# MAGI_sBuckPower-TEST_-.net
KiCad netlist of a schematic drawn in Altium Designer
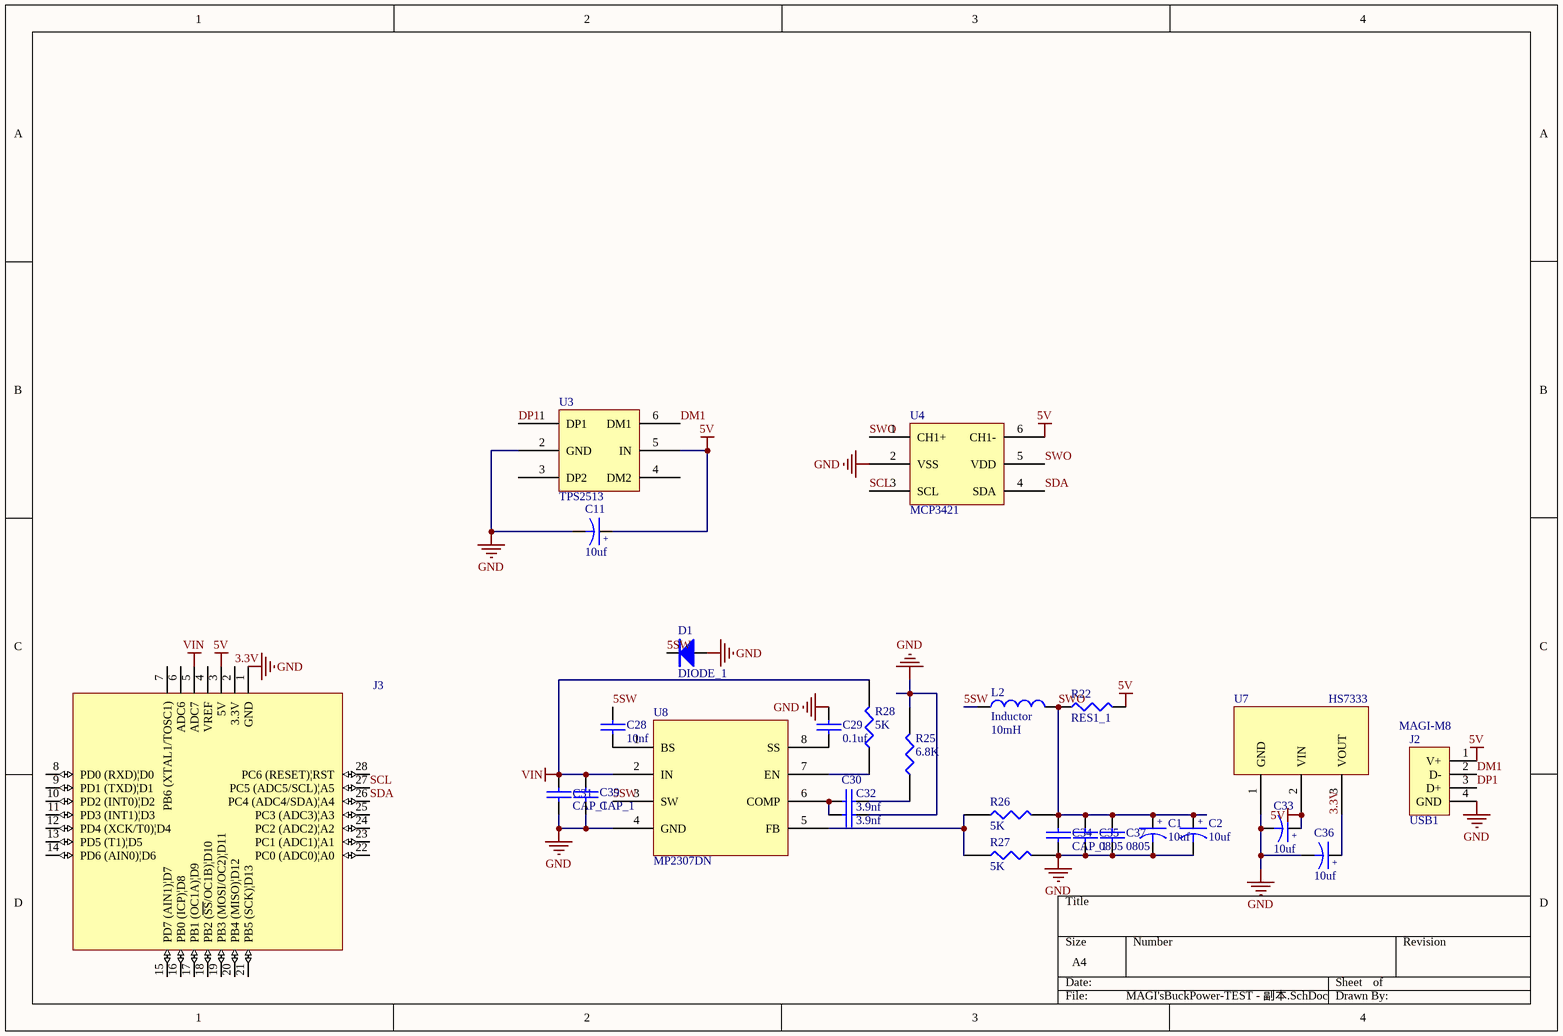
[diagram p0: MAGI'sBuckPower-TEST - 副本.SchDoc]

(export (version "E")
  (design (tool "Eeschema 10.0.6"))
  (components
    (comp (ref "C1")
      (value "10uf")
      (footprint "C1210_N")
      (description "Capacitor")
      (libsource (lib "电容器") (part "CAPACITOR POL"))
    )
    (comp (ref "C2")
      (value "10uf")
      (footprint "C1210_N")
      (description "Capacitor")
      (libsource (lib "电容器") (part "CAPACITOR POL"))
    )
    (comp (ref "C11")
      (value "10uf")
      (footprint "6-0805_N")
      (description "Capacitor")
      (libsource (lib "电容器") (part "CAPACITOR POL"))
    )
    (comp (ref "C28")
      (value "10nf")
      (footprint "6-0805_N")
      (description "Capacitor")
      (libsource (lib "电容器") (part "CAP_1"))
    )
    (comp (ref "C29")
      (value "0.1uf")
      (footprint "6-0805_N")
      (description "Capacitor")
      (libsource (lib "电容器") (part "CAP_1"))
    )
    (comp (ref "C30")
      (value "3.9nf")
      (footprint "6-0805_N")
      (description "Capacitor")
      (libsource (lib "电容器") (part "CAP_1"))
    )
    (comp (ref "C31")
      (value "CAP_1")
      (footprint "C1206")
      (description "Capacitor")
      (libsource (lib "电容器") (part "CAP_1"))
    )
    (comp (ref "C32")
      (value "3.9nf")
      (footprint "6-0805_N")
      (description "Capacitor")
      (libsource (lib "电容器") (part "CAP_1"))
    )
    (comp (ref "C33")
      (value "10uf")
      (footprint "6-0805_N")
      (description "Capacitor")
      (libsource (lib "电容器") (part "CAPACITOR POL"))
    )
    (comp (ref "C34")
      (value "CAP_1")
      (footprint "6TPE330M")
      (description "Capacitor")
      (libsource (lib "电容器") (part "CAP_1"))
    )
    (comp (ref "C35")
      (value "0805")
      (footprint "6-0805_N")
      (description "Capacitor")
      (libsource (lib "电容器") (part "CAP_1"))
    )
    (comp (ref "C36")
      (value "10uf")
      (footprint "6-0805_N")
      (description "Capacitor")
      (libsource (lib "电容器") (part "CAPACITOR POL"))
    )
    (comp (ref "C37")
      (value "0805")
      (footprint "6-0805_N")
      (description "Capacitor")
      (libsource (lib "电容器") (part "CAP_1"))
    )
    (comp (ref "C39")
      (value "CAP_1")
      (footprint "C1206")
      (description "Capacitor")
      (libsource (lib "电容器") (part "CAP_1"))
    )
    (comp (ref "D1")
      (value "DIODE_1")
      (footprint "SMA")
      (description "Diode")
      (libsource (lib "二极管") (part "DIODE_1"))
    )
    (comp (ref "J2") (value "USB1") (footprint "USB-04A") (libsource (lib "USB接口") (part "USB1")))
    (comp (ref "J3") (value "MAGI-M8") (footprint "MAGIsBoard") (libsource (lib "MAGI-M8") (part "MAGI-M8")))
    (comp (ref "L2")
      (value "Inductor")
      (footprint "7*7")
      (fields (field (name "ALTIUM_VALUE") "10mH") (field (name "PUBLISHER") "Altium Limited"))
      (libsource (lib "Miscellaneous Devices") (part "Inductor"))
    )
    (comp (ref "R22") (value "RES1_1") (footprint "2512") (libsource (lib "电阻器") (part "RES1_1")))
    (comp (ref "R25") (value "6.8K") (footprint "6-0805_N") (libsource (lib "电阻器") (part "RES1")))
    (comp (ref "R26") (value "5K") (footprint "6-0805_N") (libsource (lib "电阻器") (part "RES1")))
    (comp (ref "R27") (value "5K") (footprint "6-0805_N") (libsource (lib "电阻器") (part "RES1")))
    (comp (ref "R28") (value "5K") (footprint "6-0805_N") (libsource (lib "电阻器") (part "RES1")))
    (comp (ref "U3") (value "TPS2513") (footprint "TPS2513") (libsource (lib "PMIC") (part "TPS2513")))
    (comp (ref "U4") (value "MCP3421") (footprint "tps2513") (libsource (lib "ADC") (part "MCP3421")))
    (comp (ref "U7") (value "HS7333") (footprint "HS7333") (libsource (lib "PMIC") (part "HS7333")))
    (comp (ref "U8")
      (value "MP2307DN")
      (footprint "MP2307DN")
      (libsource (lib "MP2307Test") (part "MP2307DN"))
    )
  )
  (nets
    (net (code "1") (name "/3.3V") (class "Default")
      (node (ref "C36") (pin "1") (pinfunction "1_1") (pintype "passive"))
      (node (ref "J3") (pin "2") (pinfunction "3.3V_2") (pintype "power_in"))
      (node (ref "U7") (pin "3") (pinfunction "VOUT_3") (pintype "passive"))
    )
    (net (code "2") (name "/5SW") (class "Default")
      (node (ref "C28") (pin "1") (pinfunction "1_1") (pintype "passive"))
      (node (ref "D1") (pin "1") (pinfunction "K_1") (pintype "passive"))
      (node (ref "L2") (pin "1") (pinfunction "1_1") (pintype "passive"))
      (node (ref "U8") (pin "3") (pinfunction "SW_3") (pintype "passive"))
    )
    (net (code "3") (name "/DM1") (class "Default")
      (node (ref "J2") (pin "2") (pinfunction "D-_2") (pintype "passive"))
      (node (ref "U3") (pin "6") (pinfunction "DM1_6") (pintype "passive"))
    )
    (net (code "4") (name "/DP1") (class "Default")
      (node (ref "J2") (pin "3") (pinfunction "D+_3") (pintype "passive"))
      (node (ref "U3") (pin "1") (pinfunction "DP1_1") (pintype "passive"))
    )
    (net (code "5") (name "/SCL") (class "Default")
      (node (ref "J3") (pin "27") (pinfunction "PC5_(ADC5/SCL)¦A5_27") (pintype "bidirectional"))
      (node (ref "U4") (pin "3") (pinfunction "SCL_3") (pintype "passive"))
    )
    (net (code "6") (name "/SDA") (class "Default")
      (node (ref "J3") (pin "26") (pinfunction "PC4_(ADC4/SDA)¦A4_26") (pintype "bidirectional"))
      (node (ref "U4") (pin "4") (pinfunction "SDA_4") (pintype "passive"))
    )
    (net (code "7") (name "/SWO") (class "Default")
      (node (ref "C1") (pin "1") (pinfunction "1_1") (pintype "passive"))
      (node (ref "C2") (pin "1") (pinfunction "1_1") (pintype "passive"))
      (node (ref "C34") (pin "1") (pinfunction "1_1") (pintype "passive"))
      (node (ref "C35") (pin "1") (pinfunction "1_1") (pintype "passive"))
      (node (ref "C37") (pin "1") (pinfunction "1_1") (pintype "passive"))
      (node (ref "L2") (pin "2") (pinfunction "2_2") (pintype "passive"))
      (node (ref "R22") (pin "1") (pinfunction "1_1") (pintype "passive"))
      (node (ref "R26") (pin "2") (pinfunction "2_2") (pintype "passive"))
      (node (ref "U4") (pin "1") (pinfunction "CH1+_1") (pintype "passive"))
      (node (ref "U4") (pin "5") (pinfunction "VDD_5") (pintype "passive"))
    )
    (net (code "8") (name "5V") (class "Default")
      (node (ref "C11") (pin "1") (pinfunction "1_1") (pintype "passive"))
      (node (ref "C33") (pin "1") (pinfunction "1_1") (pintype "passive"))
      (node (ref "J2") (pin "1") (pinfunction "V+_1") (pintype "passive"))
      (node (ref "J3") (pin "3") (pinfunction "5V_3") (pintype "power_in"))
      (node (ref "R22") (pin "2") (pinfunction "2_2") (pintype "passive"))
      (node (ref "U3") (pin "5") (pinfunction "IN_5") (pintype "passive"))
      (node (ref "U4") (pin "6") (pinfunction "CH1-_6") (pintype "passive"))
      (node (ref "U7") (pin "2") (pinfunction "VIN_2") (pintype "passive"))
    )
    (net (code "9") (name "GND") (class "Default")
      (node (ref "C1") (pin "2") (pinfunction "2_2") (pintype "passive"))
      (node (ref "C11") (pin "2") (pinfunction "2_2") (pintype "passive"))
      (node (ref "C2") (pin "2") (pinfunction "2_2") (pintype "passive"))
      (node (ref "C29") (pin "1") (pinfunction "1_1") (pintype "passive"))
      (node (ref "C31") (pin "2") (pinfunction "2_2") (pintype "passive"))
      (node (ref "C32") (pin "2") (pinfunction "2_2") (pintype "passive"))
      (node (ref "C33") (pin "2") (pinfunction "2_2") (pintype "passive"))
      (node (ref "C34") (pin "2") (pinfunction "2_2") (pintype "passive"))
      (node (ref "C35") (pin "2") (pinfunction "2_2") (pintype "passive"))
      (node (ref "C36") (pin "2") (pinfunction "2_2") (pintype "passive"))
      (node (ref "C37") (pin "2") (pinfunction "2_2") (pintype "passive"))
      (node (ref "C39") (pin "2") (pinfunction "2_2") (pintype "passive"))
      (node (ref "D1") (pin "2") (pinfunction "A_2") (pintype "passive"))
      (node (ref "J2") (pin "4") (pinfunction "GND_4") (pintype "passive"))
      (node (ref "J3") (pin "1") (pinfunction "GND_1") (pintype "power_in"))
      (node (ref "R25") (pin "2") (pinfunction "2_2") (pintype "passive"))
      (node (ref "R27") (pin "2") (pinfunction "2_2") (pintype "passive"))
      (node (ref "U3") (pin "2") (pinfunction "GND_2") (pintype "passive"))
      (node (ref "U4") (pin "2") (pinfunction "VSS_2") (pintype "passive"))
      (node (ref "U7") (pin "1") (pinfunction "GND_1") (pintype "passive"))
      (node (ref "U8") (pin "4") (pinfunction "GND_4") (pintype "passive"))
    )
    (net (code "10") (name "Net-(C30-Pad2)") (class "Default")
      (node (ref "C30") (pin "2") (pinfunction "2_2") (pintype "passive"))
      (node (ref "R25") (pin "1") (pinfunction "1_1") (pintype "passive"))
    )
    (net (code "11") (name "Net-(U8-BS)") (class "Default")
      (node (ref "C28") (pin "2") (pinfunction "2_2") (pintype "passive"))
      (node (ref "U8") (pin "1") (pinfunction "BS_1") (pintype "passive"))
    )
    (net (code "12") (name "Net-(U8-COMP)") (class "Default")
      (node (ref "C30") (pin "1") (pinfunction "1_1") (pintype "passive"))
      (node (ref "C32") (pin "1") (pinfunction "1_1") (pintype "passive"))
      (node (ref "U8") (pin "6") (pinfunction "COMP_6") (pintype "passive"))
    )
    (net (code "13") (name "Net-(U8-EN)") (class "Default")
      (node (ref "R28") (pin "1") (pinfunction "1_1") (pintype "passive"))
      (node (ref "U8") (pin "7") (pinfunction "EN_7") (pintype "passive"))
    )
    (net (code "14") (name "Net-(U8-FB)") (class "Default")
      (node (ref "R26") (pin "1") (pinfunction "1_1") (pintype "passive"))
      (node (ref "R27") (pin "1") (pinfunction "1_1") (pintype "passive"))
      (node (ref "U8") (pin "5") (pinfunction "FB_5") (pintype "passive"))
    )
    (net (code "15") (name "Net-(U8-SS)") (class "Default")
      (node (ref "C29") (pin "2") (pinfunction "2_2") (pintype "passive"))
      (node (ref "U8") (pin "8") (pinfunction "SS_8") (pintype "passive"))
    )
    (net (code "16") (name "VIN") (class "Default")
      (node (ref "C31") (pin "1") (pinfunction "1_1") (pintype "passive"))
      (node (ref "C39") (pin "1") (pinfunction "1_1") (pintype "passive"))
      (node (ref "J3") (pin "5") (pinfunction "ADC7_5") (pintype "passive"))
      (node (ref "R28") (pin "2") (pinfunction "2_2") (pintype "passive"))
      (node (ref "U8") (pin "2") (pinfunction "IN_2") (pintype "passive"))
    )
    (net (code "17") (name "unconnected-(J3-ADC6-Pad6)") (class "Default")
      (node (ref "J3") (pin "6") (pinfunction "ADC6_6") (pintype "passive"))
    )
    (net (code "18") (name "unconnected-(J3-PB0_(ICP)¦D8-Pad16)") (class "Default")
      (node (ref "J3") (pin "16") (pinfunction "PB0_(ICP)¦D8_16") (pintype "bidirectional"))
    )
    (net (code "19") (name "unconnected-(J3-PB1_(OC1A)¦D9-Pad17)") (class "Default")
      (node (ref "J3") (pin "17") (pinfunction "PB1_(OC1A)¦D9_17") (pintype "bidirectional"))
    )
    (net (code "20") (name "unconnected-(J3-PB2_(~{SS}{slash}OC1B)¦D10-Pad18)") (class "Default")
      (node (ref "J3") (pin "18") (pinfunction "PB2_(~{SS}/OC1B)¦D10_18") (pintype "bidirectional"))
    )
    (net (code "21") (name "unconnected-(J3-PB3_(MOSI{slash}OC2)¦D11-Pad19)") (class "Default")
      (node (ref "J3") (pin "19") (pinfunction "PB3_(MOSI/OC2)¦D11_19") (pintype "bidirectional"))
    )
    (net (code "22") (name "unconnected-(J3-PB4_(MISO)¦D12-Pad20)") (class "Default")
      (node (ref "J3") (pin "20") (pinfunction "PB4_(MISO)¦D12_20") (pintype "bidirectional"))
    )
    (net (code "23") (name "unconnected-(J3-PB5_(SCK)¦D13-Pad21)") (class "Default")
      (node (ref "J3") (pin "21") (pinfunction "PB5_(SCK)¦D13_21") (pintype "bidirectional"))
    )
    (net (code "24") (name "unconnected-(J3-PB6_(XTAL1{slash}TOSC1)-Pad7)") (class "Default")
      (node (ref "J3") (pin "7") (pinfunction "PB6_(XTAL1/TOSC1)_7") (pintype "passive"))
    )
    (net (code "25") (name "unconnected-(J3-PC0_(ADC0)¦A0-Pad22)") (class "Default")
      (node (ref "J3") (pin "22") (pinfunction "PC0_(ADC0)¦A0_22") (pintype "bidirectional"))
    )
    (net (code "26") (name "unconnected-(J3-PC1_(ADC1)¦A1-Pad23)") (class "Default")
      (node (ref "J3") (pin "23") (pinfunction "PC1_(ADC1)¦A1_23") (pintype "bidirectional"))
    )
    (net (code "27") (name "unconnected-(J3-PC2_(ADC2)¦A2-Pad24)") (class "Default")
      (node (ref "J3") (pin "24") (pinfunction "PC2_(ADC2)¦A2_24") (pintype "bidirectional"))
    )
    (net (code "28") (name "unconnected-(J3-PC3_(ADC3)¦A3-Pad25)") (class "Default")
      (node (ref "J3") (pin "25") (pinfunction "PC3_(ADC3)¦A3_25") (pintype "bidirectional"))
    )
    (net (code "29") (name "unconnected-(J3-PC6_(RESET)¦RST-Pad28)") (class "Default")
      (node (ref "J3") (pin "28") (pinfunction "PC6_(RESET)¦RST_28") (pintype "bidirectional"))
    )
    (net (code "30") (name "unconnected-(J3-PD0_(RXD)¦D0-Pad8)") (class "Default")
      (node (ref "J3") (pin "8") (pinfunction "PD0_(RXD)¦D0_8") (pintype "bidirectional"))
    )
    (net (code "31") (name "unconnected-(J3-PD1_(TXD)¦D1-Pad9)") (class "Default")
      (node (ref "J3") (pin "9") (pinfunction "PD1_(TXD)¦D1_9") (pintype "bidirectional"))
    )
    (net (code "32") (name "unconnected-(J3-PD2_(INT0)¦D2-Pad10)") (class "Default")
      (node (ref "J3") (pin "10") (pinfunction "PD2_(INT0)¦D2_10") (pintype "bidirectional"))
    )
    (net (code "33") (name "unconnected-(J3-PD3_(INT1)¦D3-Pad11)") (class "Default")
      (node (ref "J3") (pin "11") (pinfunction "PD3_(INT1)¦D3_11") (pintype "bidirectional"))
    )
    (net (code "34") (name "unconnected-(J3-PD4_(XCK{slash}T0)¦D4-Pad12)") (class "Default")
      (node (ref "J3") (pin "12") (pinfunction "PD4_(XCK/T0)¦D4_12") (pintype "bidirectional"))
    )
    (net (code "35") (name "unconnected-(J3-PD5_(T1)¦D5-Pad13)") (class "Default")
      (node (ref "J3") (pin "13") (pinfunction "PD5_(T1)¦D5_13") (pintype "bidirectional"))
    )
    (net (code "36") (name "unconnected-(J3-PD6_(AIN0)¦D6-Pad14)") (class "Default")
      (node (ref "J3") (pin "14") (pinfunction "PD6_(AIN0)¦D6_14") (pintype "bidirectional"))
    )
    (net (code "37") (name "unconnected-(J3-PD7_(AIN1)¦D7-Pad15)") (class "Default")
      (node (ref "J3") (pin "15") (pinfunction "PD7_(AIN1)¦D7_15") (pintype "bidirectional"))
    )
    (net (code "38") (name "unconnected-(J3-VREF-Pad4)") (class "Default")
      (node (ref "J3") (pin "4") (pinfunction "VREF_4") (pintype "passive"))
    )
    (net (code "39") (name "unconnected-(U3-DM2-Pad4)") (class "Default")
      (node (ref "U3") (pin "4") (pinfunction "DM2_4") (pintype "passive"))
    )
    (net (code "40") (name "unconnected-(U3-DP2-Pad3)") (class "Default")
      (node (ref "U3") (pin "3") (pinfunction "DP2_3") (pintype "passive"))
    )
  )
)
